# SCH_555_Timer_50_Duty_Cycle_Compact_2022.net
KiCad netlist of a schematic drawn in EasyEDA
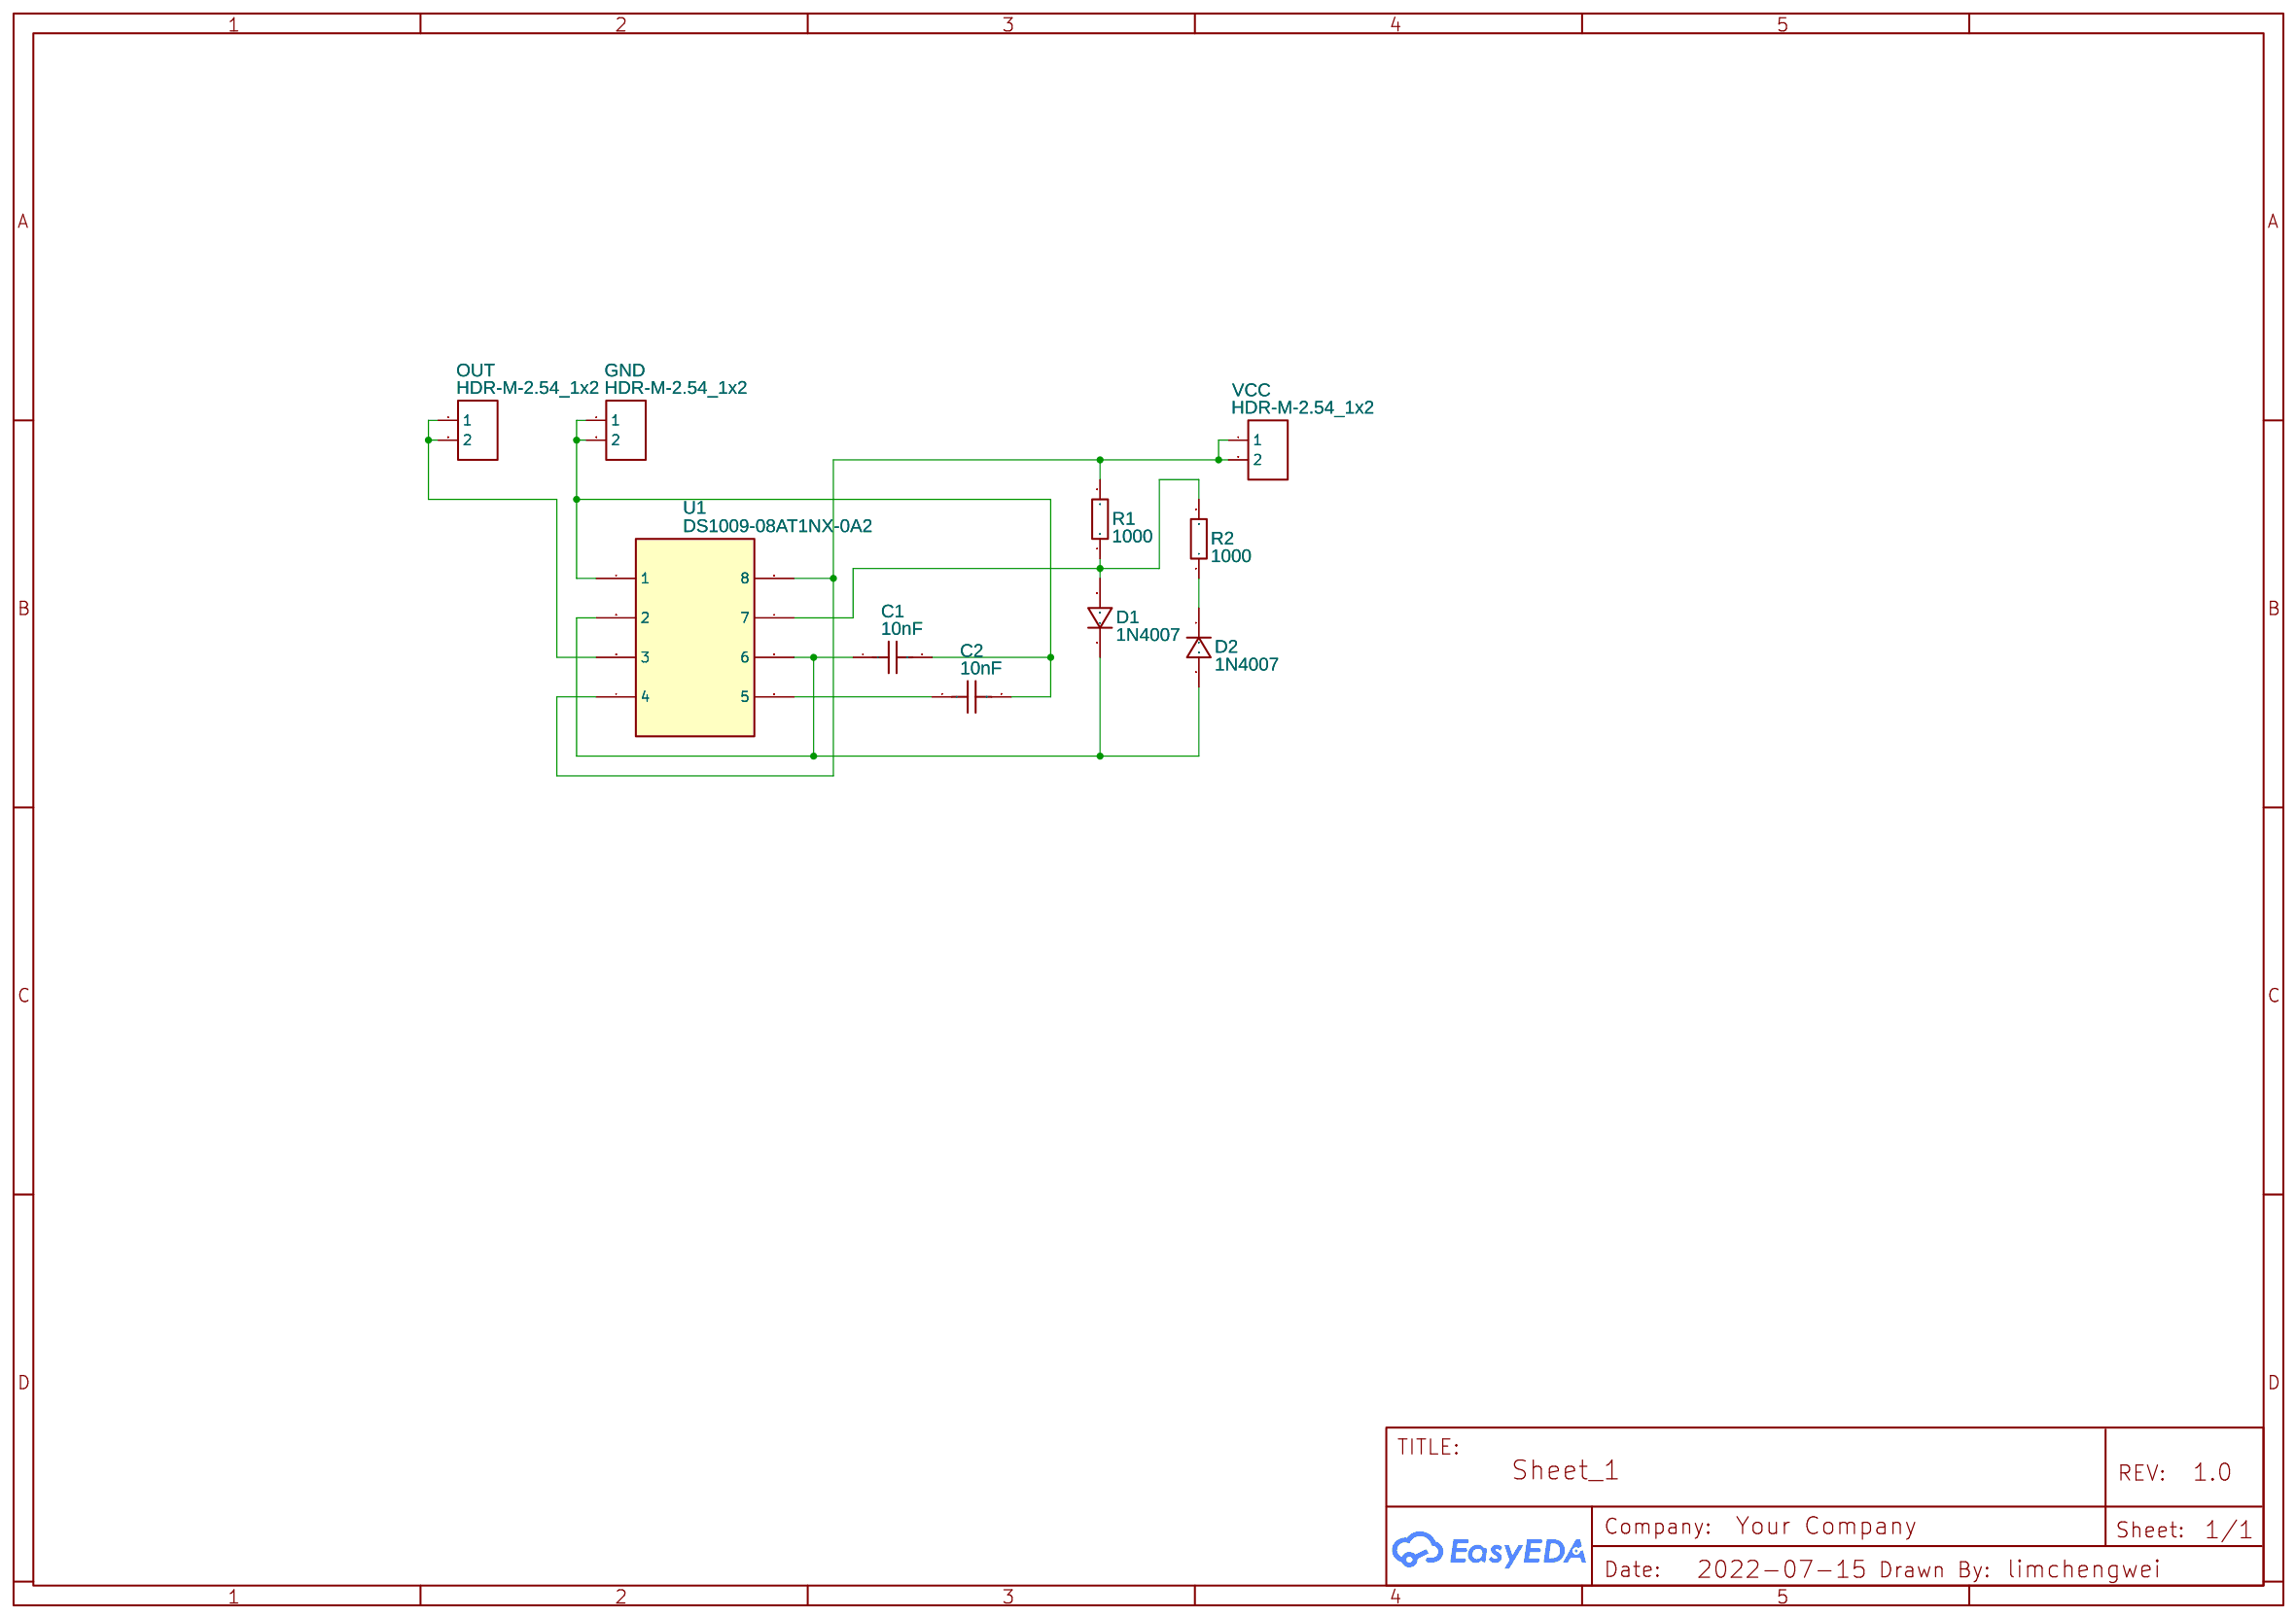
[diagram p0: schematic sheet]

(export (version "E")
  (design (tool "Eeschema 10.0.6"))
  (components
    (comp (ref "C1")
      (value "10nF")
      (fields
        (field (name "BOM_Manufacturer Part") "CC1H103MC76DB45A30S8")
        (field (name "BOM_Supplier Part") "C377837")
      )
      (libsource (lib "") (part "CC1H103MC76DB45A30S8"))
    )
    (comp (ref "C2")
      (value "10nF")
      (fields
        (field (name "BOM_Manufacturer Part") "CC1H103MC76DB45A30S8")
        (field (name "BOM_Supplier Part") "C377837")
      )
      (libsource (lib "") (part "CC1H103MC76DB45A30S8"))
    )
    (comp (ref "D1")
      (value "1N4007")
      (fields (field (name "BOM_Supplier Part") "C106903"))
      (libsource (lib "") (part "1N4007"))
    )
    (comp (ref "D2")
      (value "1N4007")
      (fields (field (name "BOM_Supplier Part") "C106903"))
      (libsource (lib "") (part "1N4007_1"))
    )
    (comp (ref "GND")
      (value "HDR-M-2.54_1x2")
      (fields (field (name "BOM_Supplier Part") "C124375"))
      (libsource (lib "") (part "HDR-M-2.54_1x2_1"))
    )
    (comp (ref "OUT")
      (value "HDR-M-2.54_1x2")
      (fields (field (name "BOM_Supplier Part") "C124375"))
      (libsource (lib "") (part "HDR-M-2.54_1x2"))
    )
    (comp (ref "R1")
      (value "1000")
      (fields (field (name "BOM_Supplier Part") "C119312"))
      (libsource (lib "") (part "MF1/4W-300Ω±1% T52"))
    )
    (comp (ref "R2")
      (value "1000")
      (fields (field (name "BOM_Supplier Part") "C119312"))
      (libsource (lib "") (part "MF1/4W-300Ω±1% T52"))
    )
    (comp (ref "U1")
      (value "DS1009-08AT1NX-0A2")
      (fields (field (name "BOM_Supplier Part") "C72124"))
      (libsource (lib "") (part "DS1009-08AT1NX-0A2"))
    )
    (comp (ref "VCC")
      (value "HDR-M-2.54_1x2")
      (fields (field (name "BOM_Supplier Part") "C124375"))
      (libsource (lib "") (part "HDR-M-2.54_1x2_2"))
    )
  )
  (nets
    (net (code "1") (name "Net-(C1-Pad1)") (class "Default")
      (node (ref "C1") (pin "1") (pinfunction "1_1") (pintype "unspecified"))
      (node (ref "D1") (pin "1") (pinfunction "1_1") (pintype "unspecified"))
      (node (ref "D2") (pin "2") (pinfunction "2_2") (pintype "unspecified"))
      (node (ref "U1") (pin "2") (pinfunction "2_2") (pintype "input"))
      (node (ref "U1") (pin "6") (pinfunction "6_6") (pintype "input"))
    )
    (net (code "2") (name "Net-(C1-Pad2)") (class "Default")
      (node (ref "C1") (pin "2") (pinfunction "2_2") (pintype "unspecified"))
      (node (ref "C2") (pin "2") (pinfunction "2_2") (pintype "unspecified"))
      (node (ref "GND") (pin "1") (pinfunction "1_1") (pintype "unspecified"))
      (node (ref "GND") (pin "2") (pinfunction "2_2") (pintype "unspecified"))
      (node (ref "U1") (pin "1") (pinfunction "1_1") (pintype "input"))
    )
    (net (code "3") (name "Net-(C2-Pad1)") (class "Default")
      (node (ref "C2") (pin "1") (pinfunction "1_1") (pintype "unspecified"))
      (node (ref "U1") (pin "5") (pinfunction "5_5") (pintype "input"))
    )
    (net (code "4") (name "Net-(D1-Pad2)") (class "Default")
      (node (ref "D1") (pin "2") (pinfunction "2_2") (pintype "unspecified"))
      (node (ref "R1") (pin "1") (pinfunction "1_1") (pintype "unspecified"))
      (node (ref "R2") (pin "2") (pinfunction "2_2") (pintype "unspecified"))
      (node (ref "U1") (pin "7") (pinfunction "7_7") (pintype "input"))
    )
    (net (code "5") (name "Net-(D2-Pad1)") (class "Default")
      (node (ref "D2") (pin "1") (pinfunction "1_1") (pintype "unspecified"))
      (node (ref "R2") (pin "1") (pinfunction "1_1") (pintype "unspecified"))
    )
    (net (code "6") (name "Net-(OUT-Pad1)") (class "Default")
      (node (ref "OUT") (pin "1") (pinfunction "1_1") (pintype "unspecified"))
      (node (ref "OUT") (pin "2") (pinfunction "2_2") (pintype "unspecified"))
      (node (ref "U1") (pin "3") (pinfunction "3_3") (pintype "input"))
    )
    (net (code "7") (name "Net-(R1-Pad2)") (class "Default")
      (node (ref "R1") (pin "2") (pinfunction "2_2") (pintype "unspecified"))
      (node (ref "U1") (pin "4") (pinfunction "4_4") (pintype "input"))
      (node (ref "U1") (pin "8") (pinfunction "8_8") (pintype "input"))
      (node (ref "VCC") (pin "1") (pinfunction "1_1") (pintype "unspecified"))
      (node (ref "VCC") (pin "2") (pinfunction "2_2") (pintype "unspecified"))
    )
  )
)
